# 2xLED_Panel.net
KiCad netlist of a schematic drawn in EAGLE
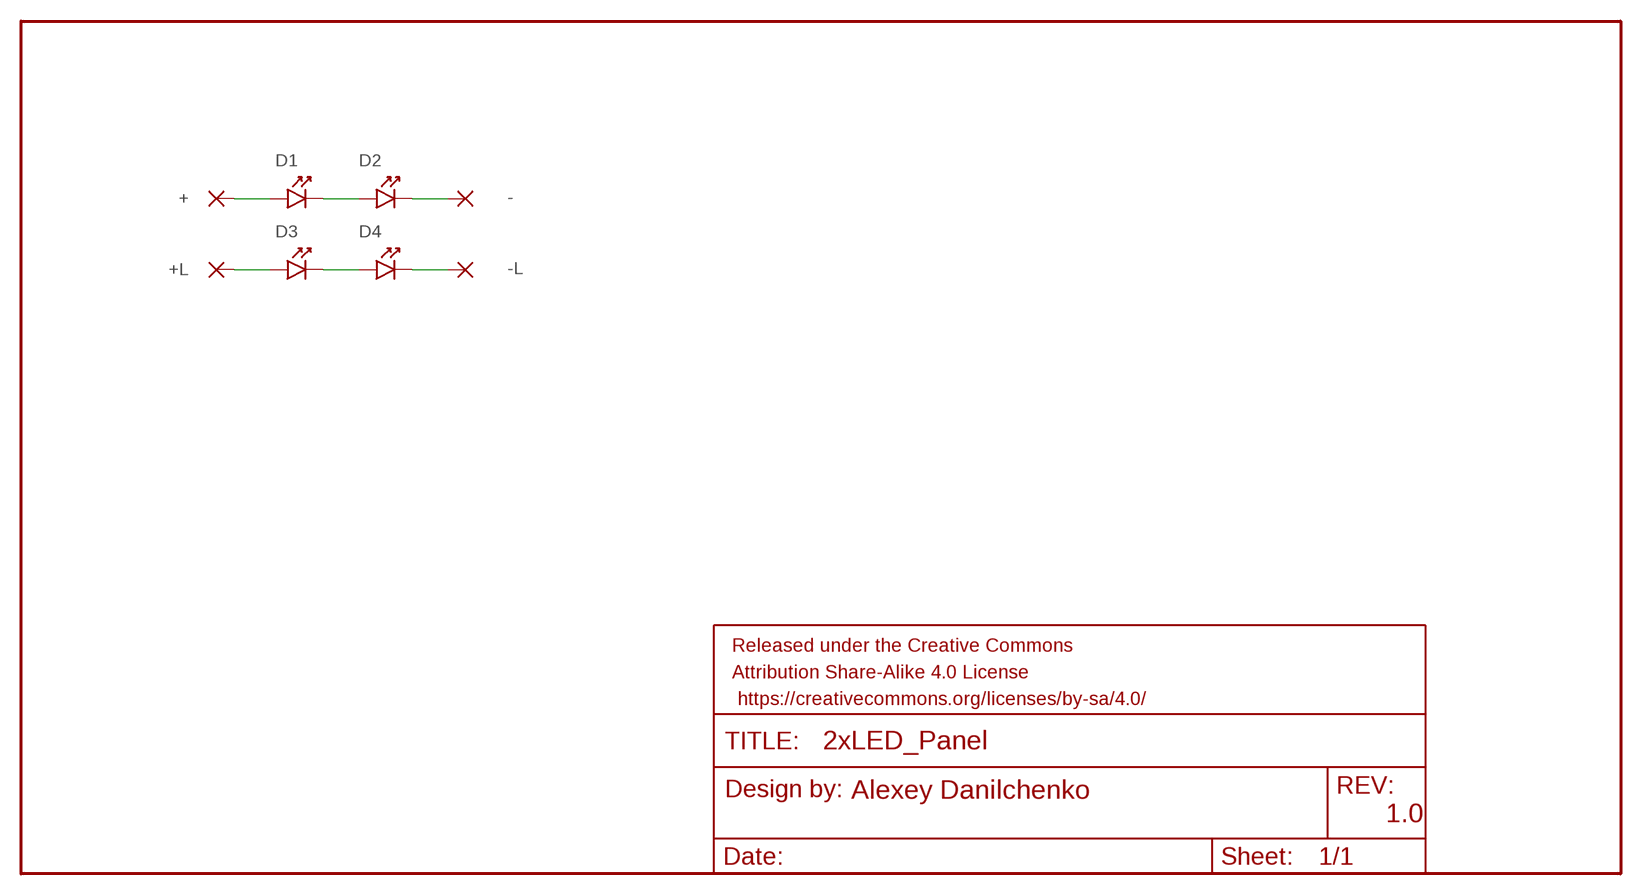
[diagram p0: schematic, sheet 1]

(export (version "E")
  (design (tool "Eeschema 10.0.6"))
  (components
    (comp (ref "+")
      (value "2,15/1,0")
      (footprint "eagle-import:2,15_1,0")
      (libsource (lib "eagle-import") (part "2,15/1,0"))
    )
    (comp (ref "+L")
      (value "2,15/1,0")
      (footprint "eagle-import:2,15_1,0")
      (libsource (lib "eagle-import") (part "2,15/1,0"))
    )
    (comp (ref "-")
      (value "2,15/1,0")
      (footprint "eagle-import:2,15_1,0")
      (libsource (lib "eagle-import") (part "2,15/1,0"))
    )
    (comp (ref "-L")
      (value "2,15/1,0")
      (footprint "eagle-import:2,15_1,0")
      (libsource (lib "eagle-import") (part "2,15/1,0"))
    )
    (comp (ref "D1")
      (value "YUJI_2835_SMD")
      (footprint "eagle-import:2835_SMD")
      (libsource (lib "eagle-import") (part "YUJI_2835_SMD"))
    )
    (comp (ref "D2")
      (value "YUJI_2835_SMD")
      (footprint "eagle-import:2835_SMD")
      (libsource (lib "eagle-import") (part "YUJI_2835_SMD"))
    )
    (comp (ref "D3")
      (value "YUJI_2835_SMD")
      (footprint "eagle-import:2835_SMD")
      (libsource (lib "eagle-import") (part "YUJI_2835_SMD"))
    )
    (comp (ref "D4")
      (value "YUJI_2835_SMD")
      (footprint "eagle-import:2835_SMD")
      (libsource (lib "eagle-import") (part "YUJI_2835_SMD"))
    )
    (comp (ref "FRAME1")
      (value "FRAME-LEDGER")
      (footprint "eagle-import:CREATIVE_COMMONS")
      (fields (field (name "AUTHOR") "Alexey Danilchenko") (field (name "VER") "1.0"))
      (libsource (lib "eagle-import") (part "FRAME-LEDGER"))
    )
  )
  (nets
    (net (code "1") (name "Net-(+-P)") (class "Default")
      (node (ref "+") (pin "1") (pinfunction "P_1") (pintype "passive"))
      (node (ref "D1") (pin "ANODE") (pinfunction "ANODE_ANODE") (pintype "bidirectional"))
    )
    (net (code "2") (name "Net-(+L-P)") (class "Default")
      (node (ref "+L") (pin "1") (pinfunction "P_1") (pintype "passive"))
      (node (ref "D3") (pin "ANODE") (pinfunction "ANODE_ANODE") (pintype "bidirectional"))
    )
    (net (code "3") (name "Net-(--P)") (class "Default")
      (node (ref "-") (pin "1") (pinfunction "P_1") (pintype "passive"))
      (node (ref "D2") (pin "CATHODE") (pinfunction "CATHODE_CATHODE") (pintype "bidirectional"))
    )
    (net (code "4") (name "Net-(-L-P)") (class "Default")
      (node (ref "-L") (pin "1") (pinfunction "P_1") (pintype "passive"))
      (node (ref "D4") (pin "CATHODE") (pinfunction "CATHODE_CATHODE") (pintype "bidirectional"))
    )
    (net (code "5") (name "Net-(D1-PadCATHODE)") (class "Default")
      (node (ref "D1") (pin "CATHODE") (pinfunction "CATHODE_CATHODE") (pintype "bidirectional"))
      (node (ref "D2") (pin "ANODE") (pinfunction "ANODE_ANODE") (pintype "bidirectional"))
    )
    (net (code "6") (name "Net-(D3-PadCATHODE)") (class "Default")
      (node (ref "D3") (pin "CATHODE") (pinfunction "CATHODE_CATHODE") (pintype "bidirectional"))
      (node (ref "D4") (pin "ANODE") (pinfunction "ANODE_ANODE") (pintype "bidirectional"))
    )
  )
)
